# steering-wheel.net
KiCad netlist of a schematic drawn in Altium Designer
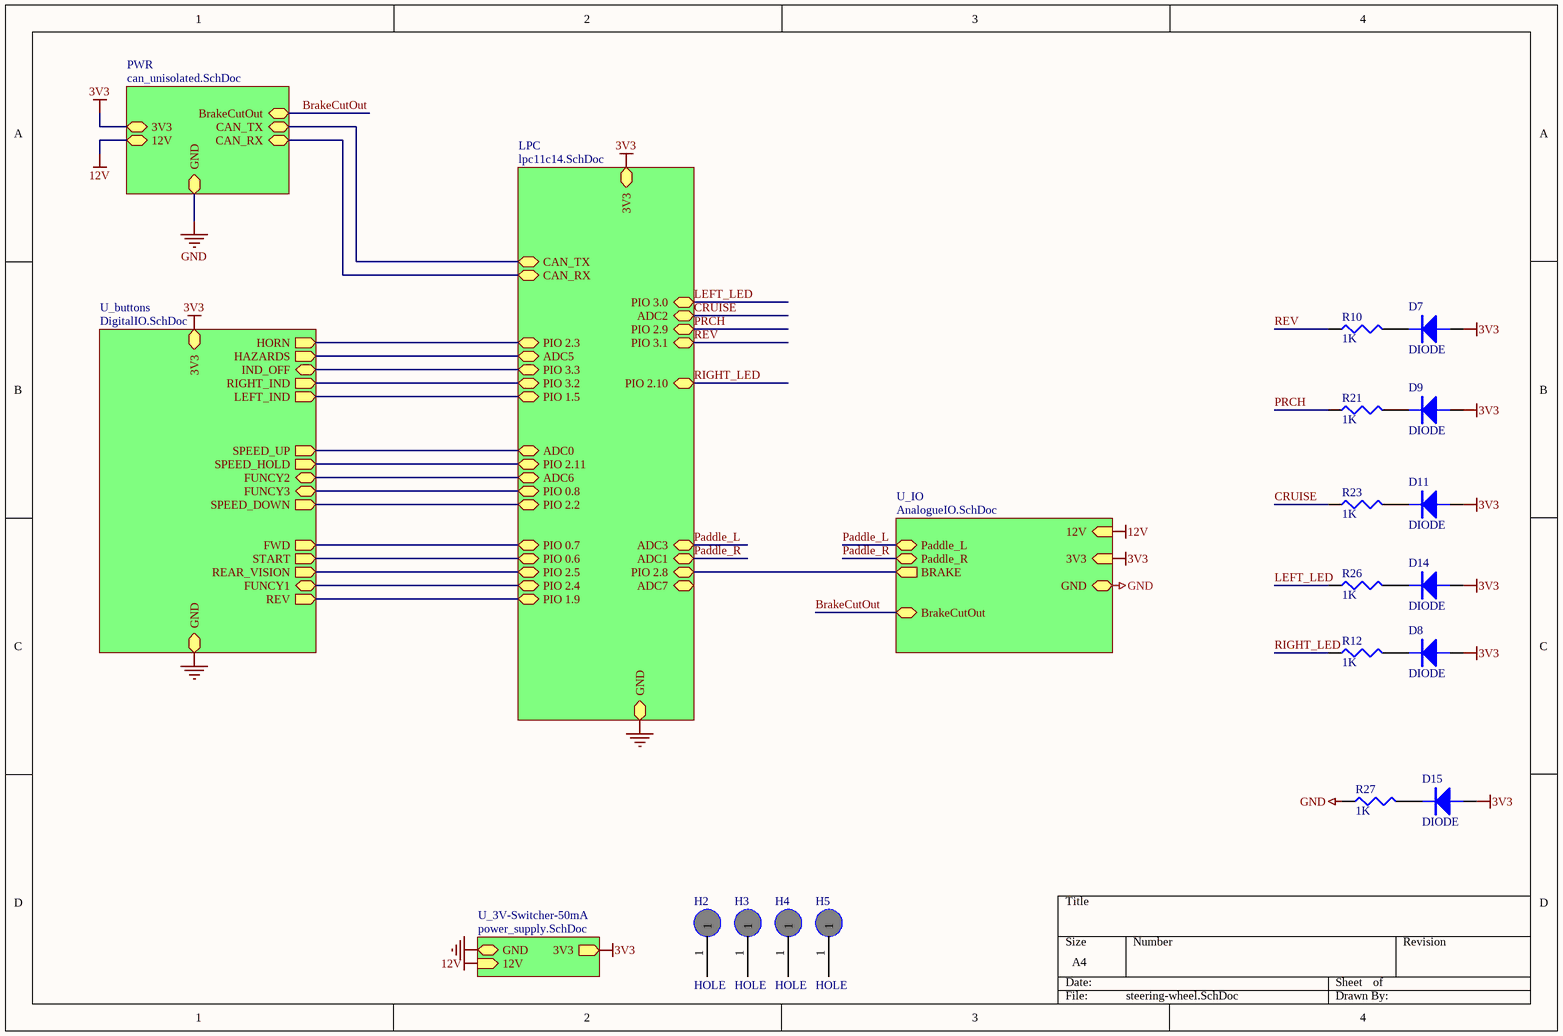
[diagram p0: steering-wheel.SchDoc]

(export (version "E")
  (design (tool "Eeschema 10.0.6"))
  (components
    (comp (ref "D7")
      (value "DIODE")
      (footprint "3m Diode")
      (description "Diode")
      (libsource (lib "RCLDQ") (part "DIODE"))
    )
    (comp (ref "D8")
      (value "DIODE")
      (footprint "3mm LED")
      (description "Diode")
      (libsource (lib "RCLDQ") (part "DIODE"))
    )
    (comp (ref "D9")
      (value "DIODE")
      (footprint "3m Diode")
      (description "Diode")
      (libsource (lib "RCLDQ") (part "DIODE"))
    )
    (comp (ref "D11")
      (value "DIODE")
      (footprint "3m Diode")
      (description "Diode")
      (libsource (lib "RCLDQ") (part "DIODE"))
    )
    (comp (ref "D14")
      (value "DIODE")
      (footprint "3m Diode")
      (description "Diode")
      (libsource (lib "RCLDQ") (part "DIODE"))
    )
    (comp (ref "D15")
      (value "DIODE")
      (footprint "3m Diode")
      (description "Diode")
      (libsource (lib "RCLDQ") (part "DIODE"))
    )
    (comp (ref "H2")
      (value "HOLE")
      (footprint "M2.5")
      (description "Hole")
      (libsource (lib "Miscellaneous") (part "HOLE"))
    )
    (comp (ref "H3")
      (value "HOLE")
      (footprint "M2.5")
      (description "Hole")
      (libsource (lib "Miscellaneous") (part "HOLE"))
    )
    (comp (ref "H4")
      (value "HOLE")
      (footprint "M2.5")
      (description "Hole")
      (libsource (lib "Miscellaneous") (part "HOLE"))
    )
    (comp (ref "H5")
      (value "HOLE")
      (footprint "M2.5")
      (description "Hole")
      (libsource (lib "Miscellaneous") (part "HOLE"))
    )
    (comp (ref "R10")
      (value "1K")
      (footprint "0603")
      (description "Resistor")
      (libsource (lib "RCLDQ") (part "RES1"))
    )
    (comp (ref "R12")
      (value "1K")
      (footprint "0603")
      (description "Resistor")
      (libsource (lib "RCLDQ") (part "RES1"))
    )
    (comp (ref "R21")
      (value "1K")
      (footprint "0603")
      (description "Resistor")
      (libsource (lib "RCLDQ") (part "RES1"))
    )
    (comp (ref "R23")
      (value "1K")
      (footprint "0603")
      (description "Resistor")
      (libsource (lib "RCLDQ") (part "RES1"))
    )
    (comp (ref "R26")
      (value "1K")
      (footprint "0603")
      (description "Resistor")
      (libsource (lib "RCLDQ") (part "RES1"))
    )
    (comp (ref "R27")
      (value "1K")
      (footprint "0603")
      (description "Resistor")
      (libsource (lib "RCLDQ") (part "RES1"))
    )
  )
  (nets
    (net (code "9") (name "/CRUISE") (class "Default")
      (node (ref "R23") (pin "1") (pinfunction "1_1") (pintype "passive"))
    )
    (net (code "16") (name "/LEFT_LED") (class "Default")
      (node (ref "R26") (pin "1") (pinfunction "1_1") (pintype "passive"))
    )
    (net (code "23") (name "/PRCH") (class "Default")
      (node (ref "R21") (pin "1") (pinfunction "1_1") (pintype "passive"))
    )
    (net (code "26") (name "/REV") (class "Default")
      (node (ref "R10") (pin "1") (pinfunction "1_1") (pintype "passive"))
    )
    (net (code "27") (name "/RIGHT_LED") (class "Default")
      (node (ref "R12") (pin "1") (pinfunction "1_1") (pintype "passive"))
    )
    (net (code "28") (name "3V3") (class "Default")
      (node (ref "D11") (pin "A") (pinfunction "A_A") (pintype "passive"))
      (node (ref "D14") (pin "A") (pinfunction "A_A") (pintype "passive"))
      (node (ref "D15") (pin "A") (pinfunction "A_A") (pintype "passive"))
      (node (ref "D7") (pin "A") (pinfunction "A_A") (pintype "passive"))
      (node (ref "D8") (pin "A") (pinfunction "A_A") (pintype "passive"))
      (node (ref "D9") (pin "A") (pinfunction "A_A") (pintype "passive"))
    )
    (net (code "30") (name "GND") (class "Default")
      (node (ref "R27") (pin "1") (pinfunction "1_1") (pintype "passive"))
    )
    (net (code "31") (name "Net-(D7-PadK)") (class "Default")
      (node (ref "D7") (pin "K") (pinfunction "K_K") (pintype "passive"))
      (node (ref "R10") (pin "2") (pinfunction "2_2") (pintype "passive"))
    )
    (net (code "32") (name "Net-(D8-PadK)") (class "Default")
      (node (ref "D8") (pin "K") (pinfunction "K_K") (pintype "passive"))
      (node (ref "R12") (pin "2") (pinfunction "2_2") (pintype "passive"))
    )
    (net (code "33") (name "Net-(D9-PadK)") (class "Default")
      (node (ref "D9") (pin "K") (pinfunction "K_K") (pintype "passive"))
      (node (ref "R21") (pin "2") (pinfunction "2_2") (pintype "passive"))
    )
    (net (code "34") (name "Net-(D11-PadK)") (class "Default")
      (node (ref "D11") (pin "K") (pinfunction "K_K") (pintype "passive"))
      (node (ref "R23") (pin "2") (pinfunction "2_2") (pintype "passive"))
    )
    (net (code "35") (name "Net-(D14-PadK)") (class "Default")
      (node (ref "D14") (pin "K") (pinfunction "K_K") (pintype "passive"))
      (node (ref "R26") (pin "2") (pinfunction "2_2") (pintype "passive"))
    )
    (net (code "36") (name "Net-(D15-PadK)") (class "Default")
      (node (ref "D15") (pin "K") (pinfunction "K_K") (pintype "passive"))
      (node (ref "R27") (pin "2") (pinfunction "2_2") (pintype "passive"))
    )
    (net (code "37") (name "unconnected-(H2-Pad1)") (class "Default")
      (node (ref "H2") (pin "1") (pinfunction "1_1") (pintype "passive"))
    )
    (net (code "38") (name "unconnected-(H3-Pad1)") (class "Default")
      (node (ref "H3") (pin "1") (pinfunction "1_1") (pintype "passive"))
    )
    (net (code "39") (name "unconnected-(H4-Pad1)") (class "Default")
      (node (ref "H4") (pin "1") (pinfunction "1_1") (pintype "passive"))
    )
    (net (code "40") (name "unconnected-(H5-Pad1)") (class "Default")
      (node (ref "H5") (pin "1") (pinfunction "1_1") (pintype "passive"))
    )
  )
)
